# POWER.net
KiCad netlist of a schematic drawn in Altium Designer
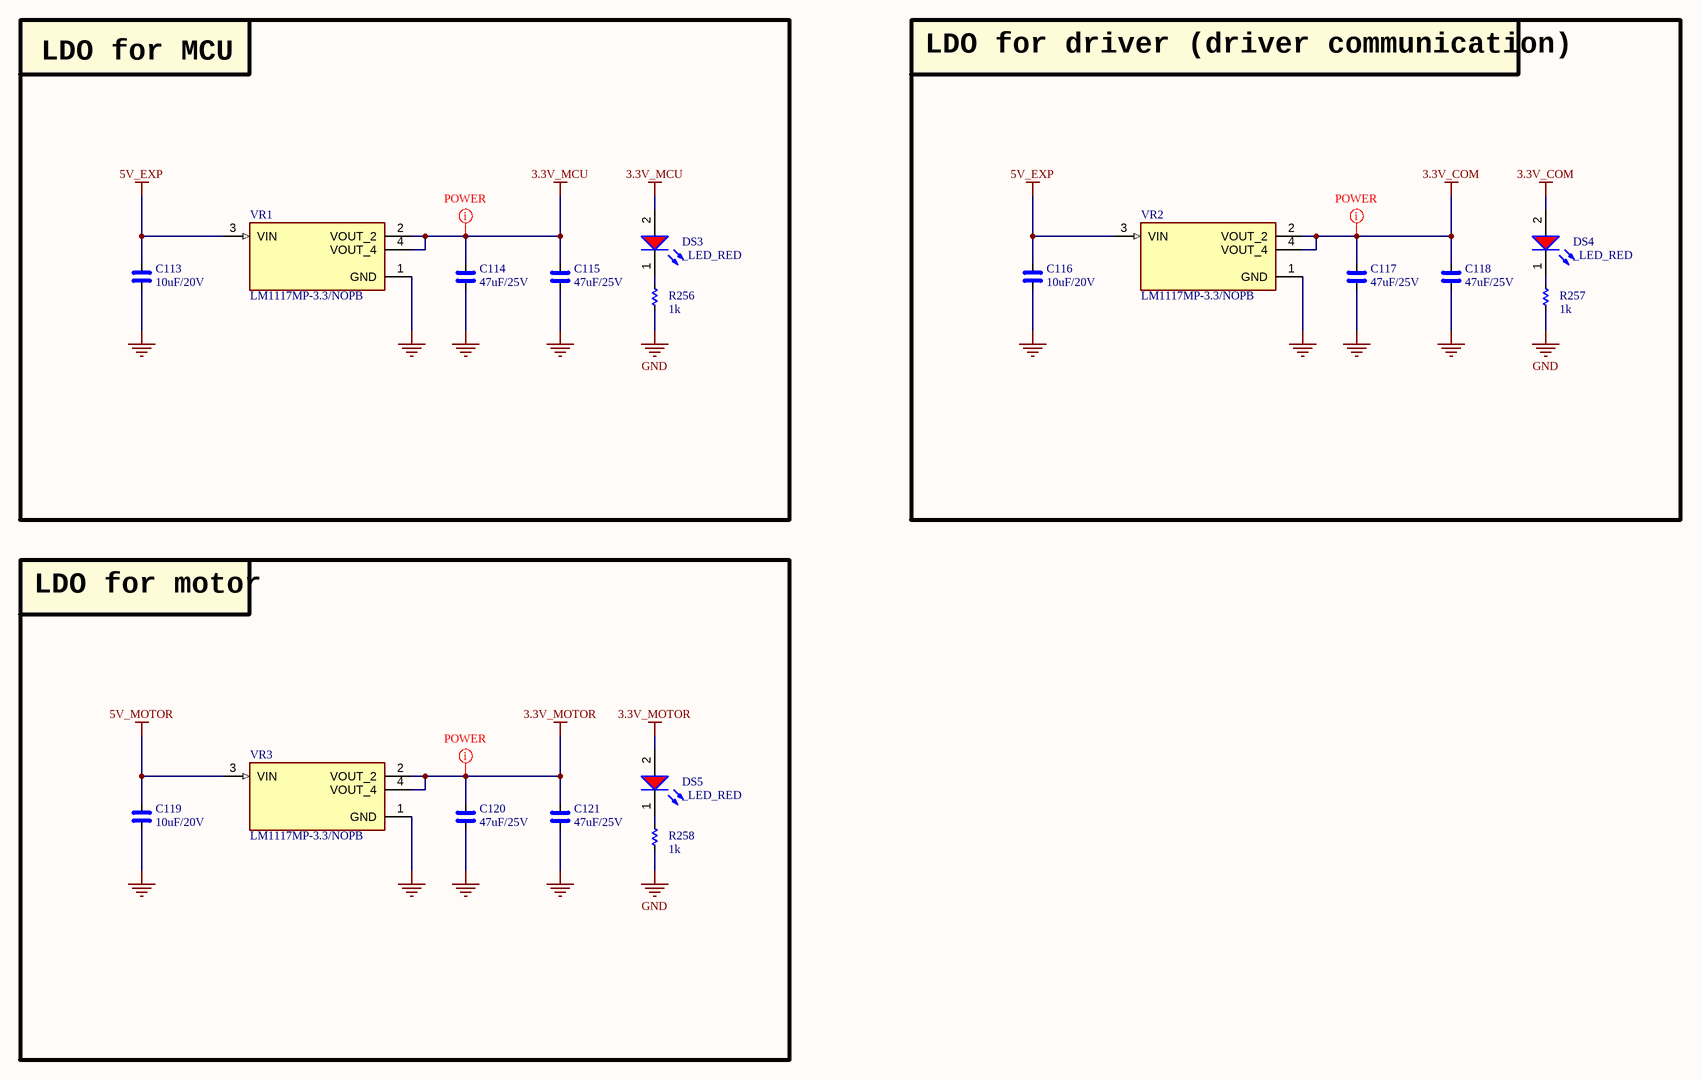
[diagram p0: POWER.SchDoc]

(export (version "E")
  (design (tool "Eeschema 10.0.6"))
  (components
    (comp (ref "C113")
      (value "10uF/20V")
      (footprint "CAP_C_2012X110")
      (description "CAP High Value")
      (libsource (lib "LABLIB") (part "_CAP_C_High_2"))
    )
    (comp (ref "C114")
      (value "47uF/25V")
      (footprint "CAP_C_3225X80")
      (description "CAP High Value")
      (libsource (lib "LABLIB") (part "_CAP_C_High_2"))
    )
    (comp (ref "C115")
      (value "47uF/25V")
      (footprint "CAP_C_3225X80")
      (description "CAP High Value")
      (libsource (lib "LABLIB") (part "_CAP_C_High_2"))
    )
    (comp (ref "C116")
      (value "10uF/20V")
      (footprint "CAP_C_2012X110")
      (description "CAP High Value")
      (libsource (lib "LABLIB") (part "_CAP_C_High_2"))
    )
    (comp (ref "C117")
      (value "47uF/25V")
      (footprint "CAP_C_3225X80")
      (description "CAP High Value")
      (libsource (lib "LABLIB") (part "_CAP_C_High_2"))
    )
    (comp (ref "C118")
      (value "47uF/25V")
      (footprint "CAP_C_3225X80")
      (description "CAP High Value")
      (libsource (lib "LABLIB") (part "_CAP_C_High_2"))
    )
    (comp (ref "C119")
      (value "10uF/20V")
      (footprint "CAP_C_2012X110")
      (description "CAP High Value")
      (libsource (lib "LABLIB") (part "_CAP_C_High_2"))
    )
    (comp (ref "C120")
      (value "47uF/25V")
      (footprint "CAP_C_3225X80")
      (description "CAP High Value")
      (libsource (lib "LABLIB") (part "_CAP_C_High_2"))
    )
    (comp (ref "C121")
      (value "47uF/25V")
      (footprint "CAP_C_3225X80")
      (description "CAP High Value")
      (libsource (lib "LABLIB") (part "_CAP_C_High_2"))
    )
    (comp (ref "DS3") (value "_LED_RED") (footprint "LED_0603") (libsource (lib "LABLIB") (part "_LED_RED")))
    (comp (ref "DS4") (value "_LED_RED") (footprint "LED_0603") (libsource (lib "LABLIB") (part "_LED_RED")))
    (comp (ref "DS5") (value "_LED_RED") (footprint "LED_0603") (libsource (lib "LABLIB") (part "_LED_RED")))
    (comp (ref "R256")
      (value "1k")
      (footprint "RES_C_1005X40")
      (description "RES")
      (libsource (lib "LABLIB") (part "_RES_B_2"))
    )
    (comp (ref "R257")
      (value "1k")
      (footprint "RES_C_1005X40")
      (description "RES")
      (libsource (lib "LABLIB") (part "_RES_B_2"))
    )
    (comp (ref "R258")
      (value "1k")
      (footprint "RES_C_1005X40")
      (description "RES")
      (libsource (lib "LABLIB") (part "_RES_B_2"))
    )
    (comp (ref "VR1")
      (value "LM1117MP-3.3/NOPB")
      (footprint "VREG_LM1117MP-3.3/NOPB")
      (description "800-mA 15-V linear voltage regulator")
      (fields (field (name "MF") "Texas Instruments"))
      (libsource (lib "LABLIB") (part "LM1117MP-3.3/NOPB"))
    )
    (comp (ref "VR2")
      (value "LM1117MP-3.3/NOPB")
      (footprint "VREG_LM1117MP-3.3/NOPB")
      (description "800-mA 15-V linear voltage regulator")
      (fields (field (name "MF") "Texas Instruments"))
      (libsource (lib "LABLIB") (part "LM1117MP-3.3/NOPB"))
    )
    (comp (ref "VR3")
      (value "LM1117MP-3.3/NOPB")
      (footprint "VREG_LM1117MP-3.3/NOPB")
      (description "800-mA 15-V linear voltage regulator")
      (fields (field (name "MF") "Texas Instruments"))
      (libsource (lib "LABLIB") (part "LM1117MP-3.3/NOPB"))
    )
  )
  (nets
    (net (code "1") (name "3.3V_COM") (class "Default")
      (node (ref "C117") (pin "2") (pinfunction "2_2") (pintype "passive"))
      (node (ref "C118") (pin "2") (pinfunction "2_2") (pintype "passive"))
      (node (ref "DS4") (pin "2") (pinfunction "A_2") (pintype "passive"))
      (node (ref "VR2") (pin "2") (pinfunction "VOUT_2_2") (pintype "power_in"))
      (node (ref "VR2") (pin "4") (pinfunction "VOUT_4_4") (pintype "power_in"))
    )
    (net (code "2") (name "3.3V_MCU") (class "Default")
      (node (ref "C114") (pin "2") (pinfunction "2_2") (pintype "passive"))
      (node (ref "C115") (pin "2") (pinfunction "2_2") (pintype "passive"))
      (node (ref "DS3") (pin "2") (pinfunction "A_2") (pintype "passive"))
      (node (ref "VR1") (pin "2") (pinfunction "VOUT_2_2") (pintype "power_in"))
      (node (ref "VR1") (pin "4") (pinfunction "VOUT_4_4") (pintype "power_in"))
    )
    (net (code "3") (name "3.3V_MOTOR") (class "Default")
      (node (ref "C120") (pin "2") (pinfunction "2_2") (pintype "passive"))
      (node (ref "C121") (pin "2") (pinfunction "2_2") (pintype "passive"))
      (node (ref "DS5") (pin "2") (pinfunction "A_2") (pintype "passive"))
      (node (ref "VR3") (pin "2") (pinfunction "VOUT_2_2") (pintype "power_in"))
      (node (ref "VR3") (pin "4") (pinfunction "VOUT_4_4") (pintype "power_in"))
    )
    (net (code "4") (name "5V_EXP") (class "Default")
      (node (ref "C113") (pin "1") (pinfunction "1_1") (pintype "passive"))
      (node (ref "C116") (pin "1") (pinfunction "1_1") (pintype "passive"))
      (node (ref "VR1") (pin "3") (pinfunction "VIN_3") (pintype "input"))
      (node (ref "VR2") (pin "3") (pinfunction "VIN_3") (pintype "input"))
    )
    (net (code "5") (name "5V_MOTOR") (class "Default")
      (node (ref "C119") (pin "1") (pinfunction "1_1") (pintype "passive"))
      (node (ref "VR3") (pin "3") (pinfunction "VIN_3") (pintype "input"))
    )
    (net (code "6") (name "GND") (class "Default")
      (node (ref "C113") (pin "2") (pinfunction "2_2") (pintype "passive"))
      (node (ref "C114") (pin "1") (pinfunction "1_1") (pintype "passive"))
      (node (ref "C115") (pin "1") (pinfunction "1_1") (pintype "passive"))
      (node (ref "C116") (pin "2") (pinfunction "2_2") (pintype "passive"))
      (node (ref "C117") (pin "1") (pinfunction "1_1") (pintype "passive"))
      (node (ref "C118") (pin "1") (pinfunction "1_1") (pintype "passive"))
      (node (ref "C119") (pin "2") (pinfunction "2_2") (pintype "passive"))
      (node (ref "C120") (pin "1") (pinfunction "1_1") (pintype "passive"))
      (node (ref "C121") (pin "1") (pinfunction "1_1") (pintype "passive"))
      (node (ref "R256") (pin "1") (pinfunction "1_1") (pintype "passive"))
      (node (ref "R257") (pin "1") (pinfunction "1_1") (pintype "passive"))
      (node (ref "R258") (pin "1") (pinfunction "1_1") (pintype "passive"))
      (node (ref "VR1") (pin "1") (pinfunction "GND_1") (pintype "power_in"))
      (node (ref "VR2") (pin "1") (pinfunction "GND_1") (pintype "power_in"))
      (node (ref "VR3") (pin "1") (pinfunction "GND_1") (pintype "power_in"))
    )
    (net (code "7") (name "Net-(DS3-K)") (class "Default")
      (node (ref "DS3") (pin "1") (pinfunction "K_1") (pintype "passive"))
      (node (ref "R256") (pin "2") (pinfunction "2_2") (pintype "passive"))
    )
    (net (code "8") (name "Net-(DS4-K)") (class "Default")
      (node (ref "DS4") (pin "1") (pinfunction "K_1") (pintype "passive"))
      (node (ref "R257") (pin "2") (pinfunction "2_2") (pintype "passive"))
    )
    (net (code "9") (name "Net-(DS5-K)") (class "Default")
      (node (ref "DS5") (pin "1") (pinfunction "K_1") (pintype "passive"))
      (node (ref "R258") (pin "2") (pinfunction "2_2") (pintype "passive"))
    )
  )
)
